# Mainboard_Motordriver_Interface.net
KiCad netlist of a schematic drawn in Altium Designer
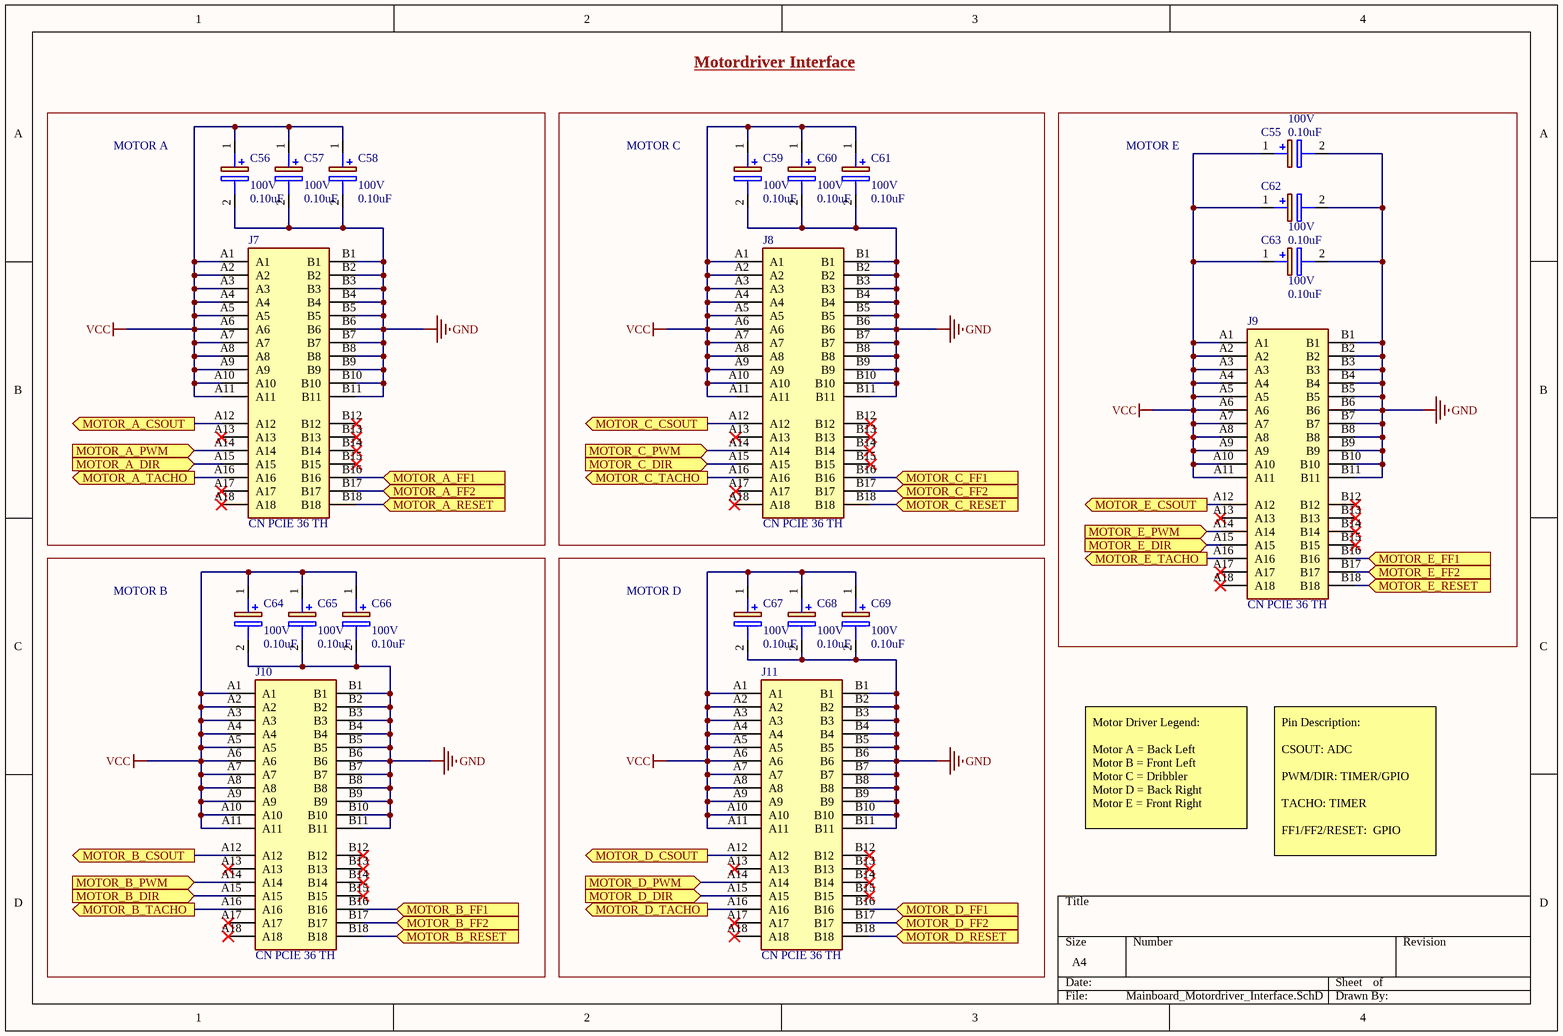
[diagram p0: Mainboard_Motordriver_Interface.SchDoc]

(export (version "E")
  (design (tool "Eeschema 10.0.6"))
  (components
    (comp (ref "C55")
      (value "0.10uF")
      (footprint "CAPPRD200W50D525H1250")
      (description "0.1µF 100V Aluminum Electrolytic Capacitors, Through-Hole, Radial, Can 2000 Hrs @ 85°C")
      (fields
        (field (name "MANUFACTURER_PART_NUMBER") "UKL2A0R1KDD")
        (field (name "MOUSER PART NUMBER") "647-UKL2A0R1KDD")
        (field (name "RATING") "100V")
      )
      (libsource (lib "AltiumLibraries") (part "CAP POL 0.1uF 100V"))
    )
    (comp (ref "C56")
      (value "0.10uF")
      (footprint "CAPPRD200W50D525H1250")
      (description "0.1µF 100V Aluminum Electrolytic Capacitors, Through-Hole, Radial, Can 2000 Hrs @ 85°C")
      (fields
        (field (name "MANUFACTURER_PART_NUMBER") "UKL2A0R1KDD")
        (field (name "MOUSER PART NUMBER") "647-UKL2A0R1KDD")
        (field (name "RATING") "100V")
      )
      (libsource (lib "") (part "CAP POL 0.1uF 100V_1"))
    )
    (comp (ref "C57")
      (value "0.10uF")
      (footprint "CAPPRD200W50D525H1250")
      (description "0.1µF 100V Aluminum Electrolytic Capacitors, Through-Hole, Radial, Can 2000 Hrs @ 85°C")
      (fields
        (field (name "MANUFACTURER_PART_NUMBER") "UKL2A0R1KDD")
        (field (name "MOUSER PART NUMBER") "647-UKL2A0R1KDD")
        (field (name "RATING") "100V")
      )
      (libsource (lib "") (part "CAP POL 0.1uF 100V_1"))
    )
    (comp (ref "C58")
      (value "0.10uF")
      (footprint "CAPPRD200W50D525H1250")
      (description "0.1µF 100V Aluminum Electrolytic Capacitors, Through-Hole, Radial, Can 2000 Hrs @ 85°C")
      (fields
        (field (name "MANUFACTURER_PART_NUMBER") "UKL2A0R1KDD")
        (field (name "MOUSER PART NUMBER") "647-UKL2A0R1KDD")
        (field (name "RATING") "100V")
      )
      (libsource (lib "") (part "CAP POL 0.1uF 100V_1"))
    )
    (comp (ref "C59")
      (value "0.10uF")
      (footprint "CAPPRD200W50D525H1250")
      (description "0.1µF 100V Aluminum Electrolytic Capacitors, Through-Hole, Radial, Can 2000 Hrs @ 85°C")
      (fields
        (field (name "MANUFACTURER_PART_NUMBER") "UKL2A0R1KDD")
        (field (name "MOUSER PART NUMBER") "647-UKL2A0R1KDD")
        (field (name "RATING") "100V")
      )
      (libsource (lib "") (part "CAP POL 0.1uF 100V_1"))
    )
    (comp (ref "C60")
      (value "0.10uF")
      (footprint "CAPPRD200W50D525H1250")
      (description "0.1µF 100V Aluminum Electrolytic Capacitors, Through-Hole, Radial, Can 2000 Hrs @ 85°C")
      (fields
        (field (name "MANUFACTURER_PART_NUMBER") "UKL2A0R1KDD")
        (field (name "MOUSER PART NUMBER") "647-UKL2A0R1KDD")
        (field (name "RATING") "100V")
      )
      (libsource (lib "") (part "CAP POL 0.1uF 100V_1"))
    )
    (comp (ref "C61")
      (value "0.10uF")
      (footprint "CAPPRD200W50D525H1250")
      (description "0.1µF 100V Aluminum Electrolytic Capacitors, Through-Hole, Radial, Can 2000 Hrs @ 85°C")
      (fields
        (field (name "MANUFACTURER_PART_NUMBER") "UKL2A0R1KDD")
        (field (name "MOUSER PART NUMBER") "647-UKL2A0R1KDD")
        (field (name "RATING") "100V")
      )
      (libsource (lib "") (part "CAP POL 0.1uF 100V_1"))
    )
    (comp (ref "C62")
      (value "0.10uF")
      (footprint "CAPPRD200W50D525H1250")
      (description "0.1µF 100V Aluminum Electrolytic Capacitors, Through-Hole, Radial, Can 2000 Hrs @ 85°C")
      (fields
        (field (name "MANUFACTURER_PART_NUMBER") "UKL2A0R1KDD")
        (field (name "MOUSER PART NUMBER") "647-UKL2A0R1KDD")
        (field (name "RATING") "100V")
      )
      (libsource (lib "AltiumLibraries") (part "CAP POL 0.1uF 100V"))
    )
    (comp (ref "C63")
      (value "0.10uF")
      (footprint "CAPPRD200W50D525H1250")
      (description "0.1µF 100V Aluminum Electrolytic Capacitors, Through-Hole, Radial, Can 2000 Hrs @ 85°C")
      (fields
        (field (name "MANUFACTURER_PART_NUMBER") "UKL2A0R1KDD")
        (field (name "MOUSER PART NUMBER") "647-UKL2A0R1KDD")
        (field (name "RATING") "100V")
      )
      (libsource (lib "AltiumLibraries") (part "CAP POL 0.1uF 100V"))
    )
    (comp (ref "C64")
      (value "0.10uF")
      (footprint "CAPPRD200W50D525H1250")
      (description "0.1µF 100V Aluminum Electrolytic Capacitors, Through-Hole, Radial, Can 2000 Hrs @ 85°C")
      (fields
        (field (name "MANUFACTURER_PART_NUMBER") "UKL2A0R1KDD")
        (field (name "MOUSER PART NUMBER") "647-UKL2A0R1KDD")
        (field (name "RATING") "100V")
      )
      (libsource (lib "") (part "CAP POL 0.1uF 100V_1"))
    )
    (comp (ref "C65")
      (value "0.10uF")
      (footprint "CAPPRD200W50D525H1250")
      (description "0.1µF 100V Aluminum Electrolytic Capacitors, Through-Hole, Radial, Can 2000 Hrs @ 85°C")
      (fields
        (field (name "MANUFACTURER_PART_NUMBER") "UKL2A0R1KDD")
        (field (name "MOUSER PART NUMBER") "647-UKL2A0R1KDD")
        (field (name "RATING") "100V")
      )
      (libsource (lib "") (part "CAP POL 0.1uF 100V_1"))
    )
    (comp (ref "C66")
      (value "0.10uF")
      (footprint "CAPPRD200W50D525H1250")
      (description "0.1µF 100V Aluminum Electrolytic Capacitors, Through-Hole, Radial, Can 2000 Hrs @ 85°C")
      (fields
        (field (name "MANUFACTURER_PART_NUMBER") "UKL2A0R1KDD")
        (field (name "MOUSER PART NUMBER") "647-UKL2A0R1KDD")
        (field (name "RATING") "100V")
      )
      (libsource (lib "") (part "CAP POL 0.1uF 100V_1"))
    )
    (comp (ref "C67")
      (value "0.10uF")
      (footprint "CAPPRD200W50D525H1250")
      (description "0.1µF 100V Aluminum Electrolytic Capacitors, Through-Hole, Radial, Can 2000 Hrs @ 85°C")
      (fields
        (field (name "MANUFACTURER_PART_NUMBER") "UKL2A0R1KDD")
        (field (name "MOUSER PART NUMBER") "647-UKL2A0R1KDD")
        (field (name "RATING") "100V")
      )
      (libsource (lib "") (part "CAP POL 0.1uF 100V_1"))
    )
    (comp (ref "C68")
      (value "0.10uF")
      (footprint "CAPPRD200W50D525H1250")
      (description "0.1µF 100V Aluminum Electrolytic Capacitors, Through-Hole, Radial, Can 2000 Hrs @ 85°C")
      (fields
        (field (name "MANUFACTURER_PART_NUMBER") "UKL2A0R1KDD")
        (field (name "MOUSER PART NUMBER") "647-UKL2A0R1KDD")
        (field (name "RATING") "100V")
      )
      (libsource (lib "") (part "CAP POL 0.1uF 100V_1"))
    )
    (comp (ref "C69")
      (value "0.10uF")
      (footprint "CAPPRD200W50D525H1250")
      (description "0.1µF 100V Aluminum Electrolytic Capacitors, Through-Hole, Radial, Can 2000 Hrs @ 85°C")
      (fields
        (field (name "MANUFACTURER_PART_NUMBER") "UKL2A0R1KDD")
        (field (name "MOUSER PART NUMBER") "647-UKL2A0R1KDD")
        (field (name "RATING") "100V")
      )
      (libsource (lib "") (part "CAP POL 0.1uF 100V_1"))
    )
    (comp (ref "J7")
      (value "CN PCIE 36 TH")
      (footprint "CN PCIE 36 TH")
      (description "36 Position Female Connector PCI Expressâ„¢ Gold 0.039 _1.00mm_ Black 10018784-10210TLF")
      (fields (field (name "MP") "10018784-10210TLF") (field (name "MF") "Amphenol ICC"))
      (libsource (lib "AltiumLibraries") (part "CN PCIE 36 TH"))
    )
    (comp (ref "J8")
      (value "CN PCIE 36 TH")
      (footprint "CN PCIE 36 TH")
      (description "36 Position Female Connector PCI Expressâ„¢ Gold 0.039 _1.00mm_ Black 10018784-10210TLF")
      (fields (field (name "MP") "10018784-10210TLF") (field (name "MF") "Amphenol ICC"))
      (libsource (lib "AltiumLibraries") (part "CN PCIE 36 TH"))
    )
    (comp (ref "J9")
      (value "CN PCIE 36 TH")
      (footprint "CN PCIE 36 TH")
      (description "36 Position Female Connector PCI Expressâ„¢ Gold 0.039 _1.00mm_ Black 10018784-10210TLF")
      (fields (field (name "MP") "10018784-10210TLF") (field (name "MF") "Amphenol ICC"))
      (libsource (lib "AltiumLibraries") (part "CN PCIE 36 TH"))
    )
    (comp (ref "J10")
      (value "CN PCIE 36 TH")
      (footprint "CN PCIE 36 TH")
      (description "36 Position Female Connector PCI Expressâ„¢ Gold 0.039 _1.00mm_ Black 10018784-10210TLF")
      (fields (field (name "MP") "10018784-10210TLF") (field (name "MF") "Amphenol ICC"))
      (libsource (lib "AltiumLibraries") (part "CN PCIE 36 TH"))
    )
    (comp (ref "J11")
      (value "CN PCIE 36 TH")
      (footprint "CN PCIE 36 TH")
      (description "36 Position Female Connector PCI Expressâ„¢ Gold 0.039 _1.00mm_ Black 10018784-10210TLF")
      (fields (field (name "MP") "10018784-10210TLF") (field (name "MF") "Amphenol ICC"))
      (libsource (lib "AltiumLibraries") (part "CN PCIE 36 TH"))
    )
  )
  (nets
    (net (code "1") (name "/MOTOR_A_CSOUT") (class "Default")
      (node (ref "J7") (pin "A12") (pinfunction "A12_A12") (pintype "passive"))
    )
    (net (code "2") (name "/MOTOR_A_DIR") (class "Default")
      (node (ref "J7") (pin "A15") (pinfunction "A15_A15") (pintype "passive"))
    )
    (net (code "3") (name "/MOTOR_A_FF1") (class "Default")
      (node (ref "J7") (pin "B16") (pinfunction "B16_B16") (pintype "passive"))
    )
    (net (code "4") (name "/MOTOR_A_FF2") (class "Default")
      (node (ref "J7") (pin "B17") (pinfunction "B17_B17") (pintype "passive"))
    )
    (net (code "5") (name "/MOTOR_A_PWM") (class "Default")
      (node (ref "J7") (pin "A14") (pinfunction "A14_A14") (pintype "passive"))
    )
    (net (code "6") (name "/MOTOR_A_RESET") (class "Default")
      (node (ref "J7") (pin "B18") (pinfunction "B18_B18") (pintype "passive"))
    )
    (net (code "7") (name "/MOTOR_A_TACHO") (class "Default")
      (node (ref "J7") (pin "A16") (pinfunction "A16_A16") (pintype "passive"))
    )
    (net (code "8") (name "/MOTOR_B_CSOUT") (class "Default")
      (node (ref "J10") (pin "A12") (pinfunction "A12_A12") (pintype "passive"))
    )
    (net (code "9") (name "/MOTOR_B_DIR") (class "Default")
      (node (ref "J10") (pin "A15") (pinfunction "A15_A15") (pintype "passive"))
    )
    (net (code "10") (name "/MOTOR_B_FF1") (class "Default")
      (node (ref "J10") (pin "B16") (pinfunction "B16_B16") (pintype "passive"))
    )
    (net (code "11") (name "/MOTOR_B_FF2") (class "Default")
      (node (ref "J10") (pin "B17") (pinfunction "B17_B17") (pintype "passive"))
    )
    (net (code "12") (name "/MOTOR_B_PWM") (class "Default")
      (node (ref "J10") (pin "A14") (pinfunction "A14_A14") (pintype "passive"))
    )
    (net (code "13") (name "/MOTOR_B_RESET") (class "Default")
      (node (ref "J10") (pin "B18") (pinfunction "B18_B18") (pintype "passive"))
    )
    (net (code "14") (name "/MOTOR_B_TACHO") (class "Default")
      (node (ref "J10") (pin "A16") (pinfunction "A16_A16") (pintype "passive"))
    )
    (net (code "15") (name "/MOTOR_C_CSOUT") (class "Default")
      (node (ref "J8") (pin "A12") (pinfunction "A12_A12") (pintype "passive"))
    )
    (net (code "16") (name "/MOTOR_C_DIR") (class "Default")
      (node (ref "J8") (pin "A15") (pinfunction "A15_A15") (pintype "passive"))
    )
    (net (code "17") (name "/MOTOR_C_FF1") (class "Default")
      (node (ref "J8") (pin "B16") (pinfunction "B16_B16") (pintype "passive"))
    )
    (net (code "18") (name "/MOTOR_C_FF2") (class "Default")
      (node (ref "J8") (pin "B17") (pinfunction "B17_B17") (pintype "passive"))
    )
    (net (code "19") (name "/MOTOR_C_PWM") (class "Default")
      (node (ref "J8") (pin "A14") (pinfunction "A14_A14") (pintype "passive"))
    )
    (net (code "20") (name "/MOTOR_C_RESET") (class "Default")
      (node (ref "J8") (pin "B18") (pinfunction "B18_B18") (pintype "passive"))
    )
    (net (code "21") (name "/MOTOR_C_TACHO") (class "Default")
      (node (ref "J8") (pin "A16") (pinfunction "A16_A16") (pintype "passive"))
    )
    (net (code "22") (name "/MOTOR_D_CSOUT") (class "Default")
      (node (ref "J11") (pin "A12") (pinfunction "A12_A12") (pintype "passive"))
    )
    (net (code "23") (name "/MOTOR_D_DIR") (class "Default")
      (node (ref "J11") (pin "A15") (pinfunction "A15_A15") (pintype "passive"))
    )
    (net (code "24") (name "/MOTOR_D_FF1") (class "Default")
      (node (ref "J11") (pin "B16") (pinfunction "B16_B16") (pintype "passive"))
    )
    (net (code "25") (name "/MOTOR_D_FF2") (class "Default")
      (node (ref "J11") (pin "B17") (pinfunction "B17_B17") (pintype "passive"))
    )
    (net (code "26") (name "/MOTOR_D_PWM") (class "Default")
      (node (ref "J11") (pin "A14") (pinfunction "A14_A14") (pintype "passive"))
    )
    (net (code "27") (name "/MOTOR_D_RESET") (class "Default")
      (node (ref "J11") (pin "B18") (pinfunction "B18_B18") (pintype "passive"))
    )
    (net (code "28") (name "/MOTOR_D_TACHO") (class "Default")
      (node (ref "J11") (pin "A16") (pinfunction "A16_A16") (pintype "passive"))
    )
    (net (code "29") (name "/MOTOR_E_CSOUT") (class "Default")
      (node (ref "J9") (pin "A12") (pinfunction "A12_A12") (pintype "passive"))
    )
    (net (code "30") (name "/MOTOR_E_DIR") (class "Default")
      (node (ref "J9") (pin "A15") (pinfunction "A15_A15") (pintype "passive"))
    )
    (net (code "31") (name "/MOTOR_E_FF1") (class "Default")
      (node (ref "J9") (pin "B16") (pinfunction "B16_B16") (pintype "passive"))
    )
    (net (code "32") (name "/MOTOR_E_FF2") (class "Default")
      (node (ref "J9") (pin "B17") (pinfunction "B17_B17") (pintype "passive"))
    )
    (net (code "33") (name "/MOTOR_E_PWM") (class "Default")
      (node (ref "J9") (pin "A14") (pinfunction "A14_A14") (pintype "passive"))
    )
    (net (code "34") (name "/MOTOR_E_RESET") (class "Default")
      (node (ref "J9") (pin "B18") (pinfunction "B18_B18") (pintype "passive"))
    )
    (net (code "35") (name "/MOTOR_E_TACHO") (class "Default")
      (node (ref "J9") (pin "A16") (pinfunction "A16_A16") (pintype "passive"))
    )
    (net (code "36") (name "GND") (class "Default")
      (node (ref "C55") (pin "2") (pinfunction "-_2") (pintype "passive"))
      (node (ref "C56") (pin "2") (pinfunction "-_2") (pintype "passive"))
      (node (ref "C57") (pin "2") (pinfunction "-_2") (pintype "passive"))
      (node (ref "C58") (pin "2") (pinfunction "-_2") (pintype "passive"))
      (node (ref "C59") (pin "2") (pinfunction "-_2") (pintype "passive"))
      (node (ref "C60") (pin "2") (pinfunction "-_2") (pintype "passive"))
      (node (ref "C61") (pin "2") (pinfunction "-_2") (pintype "passive"))
      (node (ref "C62") (pin "2") (pinfunction "-_2") (pintype "passive"))
      (node (ref "C63") (pin "2") (pinfunction "-_2") (pintype "passive"))
      (node (ref "C64") (pin "2") (pinfunction "-_2") (pintype "passive"))
      (node (ref "C65") (pin "2") (pinfunction "-_2") (pintype "passive"))
      (node (ref "C66") (pin "2") (pinfunction "-_2") (pintype "passive"))
      (node (ref "C67") (pin "2") (pinfunction "-_2") (pintype "passive"))
      (node (ref "C68") (pin "2") (pinfunction "-_2") (pintype "passive"))
      (node (ref "C69") (pin "2") (pinfunction "-_2") (pintype "passive"))
      (node (ref "J10") (pin "B1") (pinfunction "B1_B1") (pintype "passive"))
      (node (ref "J10") (pin "B10") (pinfunction "B10_B10") (pintype "passive"))
      (node (ref "J10") (pin "B11") (pinfunction "B11_B11") (pintype "passive"))
      (node (ref "J10") (pin "B2") (pinfunction "B2_B2") (pintype "passive"))
      (node (ref "J10") (pin "B3") (pinfunction "B3_B3") (pintype "passive"))
      (node (ref "J10") (pin "B4") (pinfunction "B4_B4") (pintype "passive"))
      (node (ref "J10") (pin "B5") (pinfunction "B5_B5") (pintype "passive"))
      (node (ref "J10") (pin "B6") (pinfunction "B6_B6") (pintype "passive"))
      (node (ref "J10") (pin "B7") (pinfunction "B7_B7") (pintype "passive"))
      (node (ref "J10") (pin "B8") (pinfunction "B8_B8") (pintype "passive"))
      (node (ref "J10") (pin "B9") (pinfunction "B9_B9") (pintype "passive"))
      (node (ref "J11") (pin "B1") (pinfunction "B1_B1") (pintype "passive"))
      (node (ref "J11") (pin "B10") (pinfunction "B10_B10") (pintype "passive"))
      (node (ref "J11") (pin "B11") (pinfunction "B11_B11") (pintype "passive"))
      (node (ref "J11") (pin "B2") (pinfunction "B2_B2") (pintype "passive"))
      (node (ref "J11") (pin "B3") (pinfunction "B3_B3") (pintype "passive"))
      (node (ref "J11") (pin "B4") (pinfunction "B4_B4") (pintype "passive"))
      (node (ref "J11") (pin "B5") (pinfunction "B5_B5") (pintype "passive"))
      (node (ref "J11") (pin "B6") (pinfunction "B6_B6") (pintype "passive"))
      (node (ref "J11") (pin "B7") (pinfunction "B7_B7") (pintype "passive"))
      (node (ref "J11") (pin "B8") (pinfunction "B8_B8") (pintype "passive"))
      (node (ref "J11") (pin "B9") (pinfunction "B9_B9") (pintype "passive"))
      (node (ref "J7") (pin "B1") (pinfunction "B1_B1") (pintype "passive"))
      (node (ref "J7") (pin "B10") (pinfunction "B10_B10") (pintype "passive"))
      (node (ref "J7") (pin "B11") (pinfunction "B11_B11") (pintype "passive"))
      (node (ref "J7") (pin "B2") (pinfunction "B2_B2") (pintype "passive"))
      (node (ref "J7") (pin "B3") (pinfunction "B3_B3") (pintype "passive"))
      (node (ref "J7") (pin "B4") (pinfunction "B4_B4") (pintype "passive"))
      (node (ref "J7") (pin "B5") (pinfunction "B5_B5") (pintype "passive"))
      (node (ref "J7") (pin "B6") (pinfunction "B6_B6") (pintype "passive"))
      (node (ref "J7") (pin "B7") (pinfunction "B7_B7") (pintype "passive"))
      (node (ref "J7") (pin "B8") (pinfunction "B8_B8") (pintype "passive"))
      (node (ref "J7") (pin "B9") (pinfunction "B9_B9") (pintype "passive"))
      (node (ref "J8") (pin "B1") (pinfunction "B1_B1") (pintype "passive"))
      (node (ref "J8") (pin "B10") (pinfunction "B10_B10") (pintype "passive"))
      (node (ref "J8") (pin "B11") (pinfunction "B11_B11") (pintype "passive"))
      (node (ref "J8") (pin "B2") (pinfunction "B2_B2") (pintype "passive"))
      (node (ref "J8") (pin "B3") (pinfunction "B3_B3") (pintype "passive"))
      (node (ref "J8") (pin "B4") (pinfunction "B4_B4") (pintype "passive"))
      (node (ref "J8") (pin "B5") (pinfunction "B5_B5") (pintype "passive"))
      (node (ref "J8") (pin "B6") (pinfunction "B6_B6") (pintype "passive"))
      (node (ref "J8") (pin "B7") (pinfunction "B7_B7") (pintype "passive"))
      (node (ref "J8") (pin "B8") (pinfunction "B8_B8") (pintype "passive"))
      (node (ref "J8") (pin "B9") (pinfunction "B9_B9") (pintype "passive"))
      (node (ref "J9") (pin "B1") (pinfunction "B1_B1") (pintype "passive"))
      (node (ref "J9") (pin "B10") (pinfunction "B10_B10") (pintype "passive"))
      (node (ref "J9") (pin "B11") (pinfunction "B11_B11") (pintype "passive"))
      (node (ref "J9") (pin "B2") (pinfunction "B2_B2") (pintype "passive"))
      (node (ref "J9") (pin "B3") (pinfunction "B3_B3") (pintype "passive"))
      (node (ref "J9") (pin "B4") (pinfunction "B4_B4") (pintype "passive"))
      (node (ref "J9") (pin "B5") (pinfunction "B5_B5") (pintype "passive"))
      (node (ref "J9") (pin "B6") (pinfunction "B6_B6") (pintype "passive"))
      (node (ref "J9") (pin "B7") (pinfunction "B7_B7") (pintype "passive"))
      (node (ref "J9") (pin "B8") (pinfunction "B8_B8") (pintype "passive"))
      (node (ref "J9") (pin "B9") (pinfunction "B9_B9") (pintype "passive"))
    )
    (net (code "37") (name "VCC") (class "Default")
      (node (ref "C55") (pin "1") (pinfunction "+_1") (pintype "passive"))
      (node (ref "C56") (pin "1") (pinfunction "+_1") (pintype "passive"))
      (node (ref "C57") (pin "1") (pinfunction "+_1") (pintype "passive"))
      (node (ref "C58") (pin "1") (pinfunction "+_1") (pintype "passive"))
      (node (ref "C59") (pin "1") (pinfunction "+_1") (pintype "passive"))
      (node (ref "C60") (pin "1") (pinfunction "+_1") (pintype "passive"))
      (node (ref "C61") (pin "1") (pinfunction "+_1") (pintype "passive"))
      (node (ref "C62") (pin "1") (pinfunction "+_1") (pintype "passive"))
      (node (ref "C63") (pin "1") (pinfunction "+_1") (pintype "passive"))
      (node (ref "C64") (pin "1") (pinfunction "+_1") (pintype "passive"))
      (node (ref "C65") (pin "1") (pinfunction "+_1") (pintype "passive"))
      (node (ref "C66") (pin "1") (pinfunction "+_1") (pintype "passive"))
      (node (ref "C67") (pin "1") (pinfunction "+_1") (pintype "passive"))
      (node (ref "C68") (pin "1") (pinfunction "+_1") (pintype "passive"))
      (node (ref "C69") (pin "1") (pinfunction "+_1") (pintype "passive"))
      (node (ref "J10") (pin "A1") (pinfunction "A1_A1") (pintype "passive"))
      (node (ref "J10") (pin "A10") (pinfunction "A10_A10") (pintype "passive"))
      (node (ref "J10") (pin "A11") (pinfunction "A11_A11") (pintype "passive"))
      (node (ref "J10") (pin "A2") (pinfunction "A2_A2") (pintype "passive"))
      (node (ref "J10") (pin "A3") (pinfunction "A3_A3") (pintype "passive"))
      (node (ref "J10") (pin "A4") (pinfunction "A4_A4") (pintype "passive"))
      (node (ref "J10") (pin "A5") (pinfunction "A5_A5") (pintype "passive"))
      (node (ref "J10") (pin "A6") (pinfunction "A6_A6") (pintype "passive"))
      (node (ref "J10") (pin "A7") (pinfunction "A7_A7") (pintype "passive"))
      (node (ref "J10") (pin "A8") (pinfunction "A8_A8") (pintype "passive"))
      (node (ref "J10") (pin "A9") (pinfunction "A9_A9") (pintype "passive"))
      (node (ref "J11") (pin "A1") (pinfunction "A1_A1") (pintype "passive"))
      (node (ref "J11") (pin "A10") (pinfunction "A10_A10") (pintype "passive"))
      (node (ref "J11") (pin "A11") (pinfunction "A11_A11") (pintype "passive"))
      (node (ref "J11") (pin "A2") (pinfunction "A2_A2") (pintype "passive"))
      (node (ref "J11") (pin "A3") (pinfunction "A3_A3") (pintype "passive"))
      (node (ref "J11") (pin "A4") (pinfunction "A4_A4") (pintype "passive"))
      (node (ref "J11") (pin "A5") (pinfunction "A5_A5") (pintype "passive"))
      (node (ref "J11") (pin "A6") (pinfunction "A6_A6") (pintype "passive"))
      (node (ref "J11") (pin "A7") (pinfunction "A7_A7") (pintype "passive"))
      (node (ref "J11") (pin "A8") (pinfunction "A8_A8") (pintype "passive"))
      (node (ref "J11") (pin "A9") (pinfunction "A9_A9") (pintype "passive"))
      (node (ref "J7") (pin "A1") (pinfunction "A1_A1") (pintype "passive"))
      (node (ref "J7") (pin "A10") (pinfunction "A10_A10") (pintype "passive"))
      (node (ref "J7") (pin "A11") (pinfunction "A11_A11") (pintype "passive"))
      (node (ref "J7") (pin "A2") (pinfunction "A2_A2") (pintype "passive"))
      (node (ref "J7") (pin "A3") (pinfunction "A3_A3") (pintype "passive"))
      (node (ref "J7") (pin "A4") (pinfunction "A4_A4") (pintype "passive"))
      (node (ref "J7") (pin "A5") (pinfunction "A5_A5") (pintype "passive"))
      (node (ref "J7") (pin "A6") (pinfunction "A6_A6") (pintype "passive"))
      (node (ref "J7") (pin "A7") (pinfunction "A7_A7") (pintype "passive"))
      (node (ref "J7") (pin "A8") (pinfunction "A8_A8") (pintype "passive"))
      (node (ref "J7") (pin "A9") (pinfunction "A9_A9") (pintype "passive"))
      (node (ref "J8") (pin "A1") (pinfunction "A1_A1") (pintype "passive"))
      (node (ref "J8") (pin "A10") (pinfunction "A10_A10") (pintype "passive"))
      (node (ref "J8") (pin "A11") (pinfunction "A11_A11") (pintype "passive"))
      (node (ref "J8") (pin "A2") (pinfunction "A2_A2") (pintype "passive"))
      (node (ref "J8") (pin "A3") (pinfunction "A3_A3") (pintype "passive"))
      (node (ref "J8") (pin "A4") (pinfunction "A4_A4") (pintype "passive"))
      (node (ref "J8") (pin "A5") (pinfunction "A5_A5") (pintype "passive"))
      (node (ref "J8") (pin "A6") (pinfunction "A6_A6") (pintype "passive"))
      (node (ref "J8") (pin "A7") (pinfunction "A7_A7") (pintype "passive"))
      (node (ref "J8") (pin "A8") (pinfunction "A8_A8") (pintype "passive"))
      (node (ref "J8") (pin "A9") (pinfunction "A9_A9") (pintype "passive"))
      (node (ref "J9") (pin "A1") (pinfunction "A1_A1") (pintype "passive"))
      (node (ref "J9") (pin "A10") (pinfunction "A10_A10") (pintype "passive"))
      (node (ref "J9") (pin "A11") (pinfunction "A11_A11") (pintype "passive"))
      (node (ref "J9") (pin "A2") (pinfunction "A2_A2") (pintype "passive"))
      (node (ref "J9") (pin "A3") (pinfunction "A3_A3") (pintype "passive"))
      (node (ref "J9") (pin "A4") (pinfunction "A4_A4") (pintype "passive"))
      (node (ref "J9") (pin "A5") (pinfunction "A5_A5") (pintype "passive"))
      (node (ref "J9") (pin "A6") (pinfunction "A6_A6") (pintype "passive"))
      (node (ref "J9") (pin "A7") (pinfunction "A7_A7") (pintype "passive"))
      (node (ref "J9") (pin "A8") (pinfunction "A8_A8") (pintype "passive"))
      (node (ref "J9") (pin "A9") (pinfunction "A9_A9") (pintype "passive"))
    )
    (net (code "38") (name "unconnected-(J7-PadA13)") (class "Default")
      (node (ref "J7") (pin "A13") (pinfunction "A13_A13") (pintype "passive+no_connect"))
    )
    (net (code "39") (name "unconnected-(J7-PadA17)") (class "Default")
      (node (ref "J7") (pin "A17") (pinfunction "A17_A17") (pintype "passive+no_connect"))
    )
    (net (code "40") (name "unconnected-(J7-PadA18)") (class "Default")
      (node (ref "J7") (pin "A18") (pinfunction "A18_A18") (pintype "passive+no_connect"))
    )
    (net (code "41") (name "unconnected-(J7-PadB12)") (class "Default")
      (node (ref "J7") (pin "B12") (pinfunction "B12_B12") (pintype "passive+no_connect"))
    )
    (net (code "42") (name "unconnected-(J7-PadB13)") (class "Default")
      (node (ref "J7") (pin "B13") (pinfunction "B13_B13") (pintype "passive+no_connect"))
    )
    (net (code "43") (name "unconnected-(J7-PadB14)") (class "Default")
      (node (ref "J7") (pin "B14") (pinfunction "B14_B14") (pintype "passive+no_connect"))
    )
    (net (code "44") (name "unconnected-(J7-PadB15)") (class "Default")
      (node (ref "J7") (pin "B15") (pinfunction "B15_B15") (pintype "passive+no_connect"))
    )
    (net (code "45") (name "unconnected-(J8-PadA13)") (class "Default")
      (node (ref "J8") (pin "A13") (pinfunction "A13_A13") (pintype "passive+no_connect"))
    )
    (net (code "46") (name "unconnected-(J8-PadA17)") (class "Default")
      (node (ref "J8") (pin "A17") (pinfunction "A17_A17") (pintype "passive+no_connect"))
    )
    (net (code "47") (name "unconnected-(J8-PadA18)") (class "Default")
      (node (ref "J8") (pin "A18") (pinfunction "A18_A18") (pintype "passive"))
    )
    (net (code "48") (name "unconnected-(J8-PadB12)") (class "Default")
      (node (ref "J8") (pin "B12") (pinfunction "B12_B12") (pintype "passive+no_connect"))
    )
    (net (code "49") (name "unconnected-(J8-PadB13)") (class "Default")
      (node (ref "J8") (pin "B13") (pinfunction "B13_B13") (pintype "passive+no_connect"))
    )
    (net (code "50") (name "unconnected-(J8-PadB14)") (class "Default")
      (node (ref "J8") (pin "B14") (pinfunction "B14_B14") (pintype "passive"))
    )
    (net (code "51") (name "unconnected-(J8-PadB15)") (class "Default")
      (node (ref "J8") (pin "B15") (pinfunction "B15_B15") (pintype "passive+no_connect"))
    )
    (net (code "52") (name "unconnected-(J9-PadA13)") (class "Default")
      (node (ref "J9") (pin "A13") (pinfunction "A13_A13") (pintype "passive+no_connect"))
    )
    (net (code "53") (name "unconnected-(J9-PadA17)") (class "Default")
      (node (ref "J9") (pin "A17") (pinfunction "A17_A17") (pintype "passive+no_connect"))
    )
    (net (code "54") (name "unconnected-(J9-PadA18)") (class "Default")
      (node (ref "J9") (pin "A18") (pinfunction "A18_A18") (pintype "passive+no_connect"))
    )
    (net (code "55") (name "unconnected-(J9-PadB12)") (class "Default")
      (node (ref "J9") (pin "B12") (pinfunction "B12_B12") (pintype "passive+no_connect"))
    )
    (net (code "56") (name "unconnected-(J9-PadB13)") (class "Default")
      (node (ref "J9") (pin "B13") (pinfunction "B13_B13") (pintype "passive+no_connect"))
    )
    (net (code "57") (name "unconnected-(J9-PadB14)") (class "Default")
      (node (ref "J9") (pin "B14") (pinfunction "B14_B14") (pintype "passive+no_connect"))
    )
    (net (code "58") (name "unconnected-(J9-PadB15)") (class "Default")
      (node (ref "J9") (pin "B15") (pinfunction "B15_B15") (pintype "passive+no_connect"))
    )
    (net (code "59") (name "unconnected-(J10-PadA13)") (class "Default")
      (node (ref "J10") (pin "A13") (pinfunction "A13_A13") (pintype "passive+no_connect"))
    )
    (net (code "60") (name "unconnected-(J10-PadA17)") (class "Default")
      (node (ref "J10") (pin "A17") (pinfunction "A17_A17") (pintype "passive+no_connect"))
    )
    (net (code "61") (name "unconnected-(J10-PadA18)") (class "Default")
      (node (ref "J10") (pin "A18") (pinfunction "A18_A18") (pintype "passive+no_connect"))
    )
    (net (code "62") (name "unconnected-(J10-PadB12)") (class "Default")
      (node (ref "J10") (pin "B12") (pinfunction "B12_B12") (pintype "passive+no_connect"))
    )
    (net (code "63") (name "unconnected-(J10-PadB13)") (class "Default")
      (node (ref "J10") (pin "B13") (pinfunction "B13_B13") (pintype "passive+no_connect"))
    )
    (net (code "64") (name "unconnected-(J10-PadB14)") (class "Default")
      (node (ref "J10") (pin "B14") (pinfunction "B14_B14") (pintype "passive+no_connect"))
    )
    (net (code "65") (name "unconnected-(J10-PadB15)") (class "Default")
      (node (ref "J10") (pin "B15") (pinfunction "B15_B15") (pintype "passive+no_connect"))
    )
    (net (code "66") (name "unconnected-(J11-PadA13)") (class "Default")
      (node (ref "J11") (pin "A13") (pinfunction "A13_A13") (pintype "passive+no_connect"))
    )
    (net (code "67") (name "unconnected-(J11-PadA17)") (class "Default")
      (node (ref "J11") (pin "A17") (pinfunction "A17_A17") (pintype "passive+no_connect"))
    )
    (net (code "68") (name "unconnected-(J11-PadA18)") (class "Default")
      (node (ref "J11") (pin "A18") (pinfunction "A18_A18") (pintype "passive+no_connect"))
    )
    (net (code "69") (name "unconnected-(J11-PadB12)") (class "Default")
      (node (ref "J11") (pin "B12") (pinfunction "B12_B12") (pintype "passive+no_connect"))
    )
    (net (code "70") (name "unconnected-(J11-PadB13)") (class "Default")
      (node (ref "J11") (pin "B13") (pinfunction "B13_B13") (pintype "passive+no_connect"))
    )
    (net (code "71") (name "unconnected-(J11-PadB14)") (class "Default")
      (node (ref "J11") (pin "B14") (pinfunction "B14_B14") (pintype "passive+no_connect"))
    )
    (net (code "72") (name "unconnected-(J11-PadB15)") (class "Default")
      (node (ref "J11") (pin "B15") (pinfunction "B15_B15") (pintype "passive+no_connect"))
    )
  )
)
